# Charging.net
KiCad netlist of a schematic drawn in Altium Designer
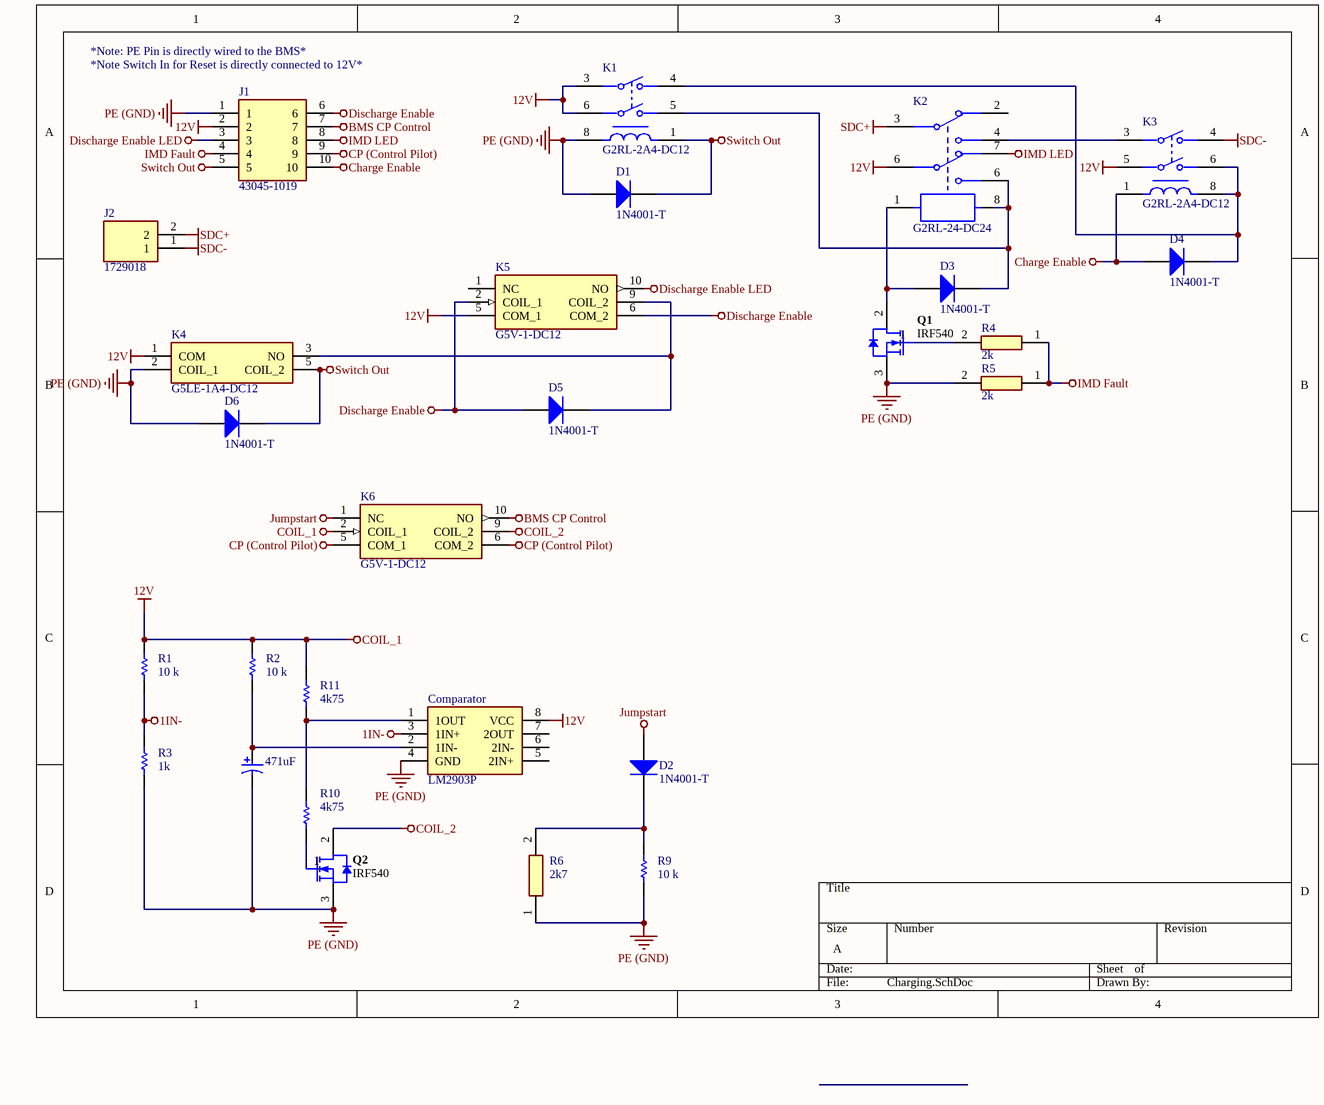
[diagram p0: Charging.SchDoc]

(export (version "E")
  (design (tool "Eeschema 10.0.6"))
  (components
    (comp (ref "471uF")
      (value "ECA-1JHG471")
      (footprint "CAPPR65-500-2000X1250X2200")
      (fields (field (name "MANUFACTURER") "Panasonic"))
      (libsource (lib "Altium Content Vault") (part "CAP-P-2"))
    )
    (comp (ref "Comparator")
      (value "LM2903P")
      (footprint "SamacSys:DIP794W53P254L959H508Q8N")
      (description "Integrated Circuit")
      (fields (field (name "MOUSER PART NUMBER") "595-LM2903P"))
      (libsource (lib "*") (part "LM2903P"))
    )
    (comp (ref "D1")
      (value "1N4001-T")
      (footprint "DIOD-DO-41-P-2_V")
      (description "1.0 A Rectifier, 15 pF, 50 V, -65 to 150 degC, 2-Pin DO-41 Plastic, RoHS, Tape and Reel")
      (fields (field (name "MANUFACTURER") "Diodes Inc"))
      (libsource (lib "Altium Content Vault") (part "DIOD-D-A1K2-2"))
    )
    (comp (ref "D2")
      (value "1N4001-T")
      (footprint "DIOD-DO-41-P-2_V")
      (description "1.0 A Rectifier, 15 pF, 50 V, -65 to 150 degC, 2-Pin DO-41 Plastic, RoHS, Tape and Reel")
      (fields (field (name "MANUFACTURER") "Diodes Inc"))
      (libsource (lib "Altium Content Vault") (part "DIOD-D-A1K2-2"))
    )
    (comp (ref "D3")
      (value "1N4001-T")
      (footprint "DIOD-DO-41-P-2_V")
      (description "1.0 A Rectifier, 15 pF, 50 V, -65 to 150 degC, 2-Pin DO-41 Plastic, RoHS, Tape and Reel")
      (fields (field (name "MANUFACTURER") "Diodes Inc"))
      (libsource (lib "Altium Content Vault") (part "DIOD-D-A1K2-2"))
    )
    (comp (ref "D4")
      (value "1N4001-T")
      (footprint "DIOD-DO-41-P-2_V")
      (description "1.0 A Rectifier, 15 pF, 50 V, -65 to 150 degC, 2-Pin DO-41 Plastic, RoHS, Tape and Reel")
      (fields (field (name "MANUFACTURER") "Diodes Inc"))
      (libsource (lib "Altium Content Vault") (part "DIOD-D-A1K2-2"))
    )
    (comp (ref "D5")
      (value "1N4001-T")
      (footprint "DIOD-DO-41-P-2_V")
      (description "1.0 A Rectifier, 15 pF, 50 V, -65 to 150 degC, 2-Pin DO-41 Plastic, RoHS, Tape and Reel")
      (fields (field (name "MANUFACTURER") "Diodes Inc"))
      (libsource (lib "Altium Content Vault") (part "DIOD-D-A1K2-2"))
    )
    (comp (ref "D6")
      (value "1N4001-T")
      (footprint "DIOD-DO-41-P-2_V")
      (description "1.0 A Rectifier, 15 pF, 50 V, -65 to 150 degC, 2-Pin DO-41 Plastic, RoHS, Tape and Reel")
      (fields (field (name "MANUFACTURER") "Diodes Inc"))
      (libsource (lib "Altium Content Vault") (part "DIOD-D-A1K2-2"))
    )
    (comp (ref "J1")
      (value "43045-1019")
      (footprint "SamacSys:43045-10YY_181920")
      (description "Connector")
      (fields (field (name "MOUSER PART NUMBER") "538-43045-1019"))
      (libsource (lib "*") (part "43045-1019"))
    )
    (comp (ref "J2")
      (value "1729018")
      (footprint "SamacSys:1729018")
      (description "Connector")
      (fields (field (name "MOUSER PART NUMBER") "651-1729018"))
      (libsource (lib "*") (part "1729018"))
    )
    (comp (ref "K1")
      (value "G2RL-2A4-DC12")
      (footprint "FP-G2RL-2A4-DC12-MFG")
      (description "RELAY GEN PURPOSE DPST 8A 12V")
      (libsource (lib "Altium Content Vault") (part "dfb52caf01785165d8ace8a37fe0b79"))
    )
    (comp (ref "K2")
      (value "G2RL-24-DC24")
      (footprint "OMRON-G2RL-24_V")
      (fields (field (name "MANUFACTURER") "Omron"))
      (libsource (lib "Altium Content Vault") (part "RELAY-DPDT-8_C"))
    )
    (comp (ref "K3")
      (value "G2RL-2A4-DC12")
      (footprint "FP-G2RL-2A4-DC12-MFG")
      (description "RELAY GEN PURPOSE DPST 8A 12V")
      (libsource (lib "") (part "dfb52caf01785165d8ace8a37fe0b79_1"))
    )
    (comp (ref "K4")
      (value "G5LE-1A4-DC12")
      (footprint "SamacSys:G5LE1A4DC12")
      (description "Relay or Contactor")
      (fields (field (name "MOUSER PART NUMBER") "653-G5LE-1A4-DC12"))
      (libsource (lib "*") (part "G5LE-1A4-DC12"))
    )
    (comp (ref "K5")
      (value "G5V-1-DC12")
      (footprint "SamacSys:G5V1DC12")
      (description "Relay or Contactor")
      (fields (field (name "MOUSER PART NUMBER") "653-G5V-1-DC12"))
      (libsource (lib "*") (part "G5V-1-DC12"))
    )
    (comp (ref "K6")
      (value "G5V-1-DC12")
      (footprint "SamacSys:G5V1DC12")
      (description "Relay or Contactor")
      (fields (field (name "MOUSER PART NUMBER") "653-G5V-1-DC12"))
      (libsource (lib "*") (part "G5V-1-DC12"))
    )
    (comp (ref "Q1")
      (value "IRF540")
      (footprint "VISH-TO-220AB-3_A")
      (description "Power MOSFET, 100 VDS, -55 to 175 degC, 3-Pin TO-220AB, RoHS, Tube")
      (fields (field (name "MANUFACTURER") "Vishay"))
      (libsource (lib "Altium Content Vault") (part "NEMOS-GDS-3"))
    )
    (comp (ref "Q2")
      (value "IRF540")
      (footprint "VISH-TO-220AB-3_A")
      (description "Power MOSFET, 100 VDS, -55 to 175 degC, 3-Pin TO-220AB, RoHS, Tube")
      (fields (field (name "MANUFACTURER") "Vishay"))
      (libsource (lib "Altium Content Vault") (part "NEMOS-GDS-3"))
    )
    (comp (ref "R1")
      (value "MFR-25FBF52-1K")
      (footprint "RESA60-630X240")
      (description "Axial Resistor, 1 KOhm, +/- 1%, 250 mW, -55 to 155 degC, 2-Pin THD, RoHS, Bulk")
      (fields (field (name "TOLERANCE") "1%") (field (name "RESISTANCE") "10 k"))
      (libsource (lib "Altium Content Vault") (part "RES-2"))
    )
    (comp (ref "R2")
      (value "MFR-25FBF52-1K")
      (footprint "RESA60-630X240")
      (description "Axial Resistor, 1 KOhm, +/- 1%, 250 mW, -55 to 155 degC, 2-Pin THD, RoHS, Bulk")
      (fields (field (name "TOLERANCE") "1%") (field (name "RESISTANCE") "10 k"))
      (libsource (lib "Altium Content Vault") (part "RES-2"))
    )
    (comp (ref "R3")
      (value "MFR-25FBF52-1K")
      (footprint "RESA60-630X240")
      (description "Axial Resistor, 1 KOhm, +/- 1%, 250 mW, -55 to 155 degC, 2-Pin THD, RoHS, Bulk")
      (fields (field (name "TOLERANCE") "1%") (field (name "RESISTANCE") "1k"))
      (libsource (lib "Altium Content Vault") (part "RES-2"))
    )
    (comp (ref "R4")
      (value "MFR-25FBF52-2K")
      (footprint "SamacSys:RESAD1590W60L630D240")
      (description "Resistor")
      (fields (field (name "RESISTANCE") "2k"))
      (libsource (lib "*") (part "MFR-25FBF52-2K"))
    )
    (comp (ref "R5")
      (value "MFR-25FBF52-2K")
      (footprint "SamacSys:RESAD1590W60L630D240")
      (description "Resistor")
      (fields (field (name "RESISTANCE") "2k"))
      (libsource (lib "*") (part "MFR-25FBF52-2K"))
    )
    (comp (ref "R6")
      (value "2.7k")
      (footprint "SamacSys:RESAD1590W60L630D240")
      (description "Resistor")
      (fields
        (field (name "MANUFACTURER_PART_NUMBER") "CFR-25JB-52-2K7")
        (field (name "MOUSER PART NUMBER") "603-CFR-25JB-52-2K7")
        (field (name "RESISTANCE") "2k7")
      )
      (libsource (lib "*") (part "CFR-25JB-52-2K7"))
    )
    (comp (ref "R9")
      (value "MFR-25FBF52-1K")
      (footprint "RESA60-630X240")
      (description "Axial Resistor, 1 KOhm, +/- 1%, 250 mW, -55 to 155 degC, 2-Pin THD, RoHS, Bulk")
      (fields (field (name "TOLERANCE") "1%") (field (name "RESISTANCE") "10 k"))
      (libsource (lib "Altium Content Vault") (part "RES-2"))
    )
    (comp (ref "R10")
      (value "4.75 k")
      (footprint "RESA60-630X240")
      (description "Axial Resistor, 4.75 KOhm, +/- 1%, 0.25 W, -55 to 155 degC, 2-Pin THD, RoHS, Bulk")
      (fields (field (name "TOLERANCE") "10%") (field (name "RESISTANCE") "4k75"))
      (libsource (lib "Altium Content Vault") (part "RES-2"))
    )
    (comp (ref "R11")
      (value "4.75 k")
      (footprint "RESA60-630X240")
      (description "Axial Resistor, 4.75 KOhm, +/- 1%, 0.25 W, -55 to 155 degC, 2-Pin THD, RoHS, Bulk")
      (fields (field (name "TOLERANCE") "10%") (field (name "RESISTANCE") "4k75"))
      (libsource (lib "Altium Content Vault") (part "RES-2"))
    )
  )
  (nets
    (net (code "1") (name "1IN-") (class "Default")
      (node (ref "Comparator") (pin "3") (pinfunction "1IN+_3") (pintype "passive"))
      (node (ref "R1") (pin "1") (pinfunction "1_1") (pintype "passive"))
      (node (ref "R3") (pin "2") (pinfunction "2_2") (pintype "passive"))
    )
    (net (code "2") (name "12V") (class "Default")
      (node (ref "Comparator") (pin "8") (pinfunction "VCC_8") (pintype "passive"))
      (node (ref "J1") (pin "2") (pinfunction "2_2") (pintype "passive"))
      (node (ref "K1") (pin "3") (pinfunction "3_3") (pintype "passive"))
      (node (ref "K1") (pin "6") (pinfunction "6_6") (pintype "passive"))
      (node (ref "K2") (pin "6") (pinfunction "6_6") (pintype "passive"))
      (node (ref "K3") (pin "5") (pinfunction "5_5") (pintype "passive"))
      (node (ref "K4") (pin "1") (pinfunction "COM_1") (pintype "passive"))
      (node (ref "K5") (pin "5") (pinfunction "COM_1_5") (pintype "passive"))
      (node (ref "K6") (pin "2") (pinfunction "COIL_1_2") (pintype "input"))
      (node (ref "R1") (pin "2") (pinfunction "2_2") (pintype "passive"))
      (node (ref "R11") (pin "2") (pinfunction "2_2") (pintype "passive"))
      (node (ref "R2") (pin "2") (pinfunction "2_2") (pintype "passive"))
    )
    (net (code "3") (name "BMS CP Control") (class "Default")
      (node (ref "J1") (pin "7") (pinfunction "7_7") (pintype "passive"))
      (node (ref "K6") (pin "10") (pinfunction "NO_10") (pintype "output"))
    )
    (net (code "4") (name "COIL_2") (class "Default")
      (node (ref "K6") (pin "9") (pinfunction "COIL_2_9") (pintype "power_in"))
      (node (ref "Q2") (pin "2") (pinfunction "D_2") (pintype "passive"))
    )
    (net (code "5") (name "CP (Control Pilot)") (class "Default")
      (node (ref "J1") (pin "9") (pinfunction "9_9") (pintype "passive"))
      (node (ref "K6") (pin "5") (pinfunction "COM_1_5") (pintype "passive"))
      (node (ref "K6") (pin "6") (pinfunction "COM_2_6") (pintype "passive"))
    )
    (net (code "6") (name "Charge Enable") (class "Default")
      (node (ref "D4") (pin "1") (pinfunction "A_1") (pintype "passive"))
      (node (ref "J1") (pin "10") (pinfunction "10_10") (pintype "passive"))
      (node (ref "K3") (pin "1") (pinfunction "1_1") (pintype "passive"))
    )
    (net (code "7") (name "Discharge Enable") (class "Default")
      (node (ref "D5") (pin "1") (pinfunction "A_1") (pintype "passive"))
      (node (ref "J1") (pin "6") (pinfunction "6_6") (pintype "passive"))
      (node (ref "K5") (pin "2") (pinfunction "COIL_1_2") (pintype "input"))
      (node (ref "K5") (pin "6") (pinfunction "COM_2_6") (pintype "passive"))
    )
    (net (code "8") (name "Discharge Enable LED") (class "Default")
      (node (ref "J1") (pin "3") (pinfunction "3_3") (pintype "passive"))
      (node (ref "K5") (pin "10") (pinfunction "NO_10") (pintype "output"))
    )
    (net (code "9") (name "IMD Fault") (class "Default")
      (node (ref "J1") (pin "4") (pinfunction "4_4") (pintype "passive"))
      (node (ref "R4") (pin "1") (pinfunction "1_1") (pintype "passive"))
      (node (ref "R5") (pin "1") (pinfunction "1_1") (pintype "passive"))
    )
    (net (code "10") (name "IMD LED") (class "Default")
      (node (ref "J1") (pin "8") (pinfunction "8_8") (pintype "passive"))
      (node (ref "K2") (pin "7") (pinfunction "7_7") (pintype "passive"))
    )
    (net (code "11") (name "Jumpstart") (class "Default")
      (node (ref "D2") (pin "1") (pinfunction "A_1") (pintype "passive"))
      (node (ref "K6") (pin "1") (pinfunction "NC_1") (pintype "passive"))
    )
    (net (code "12") (name "Net-(Comparator-1IN-)") (class "Default")
      (node (ref "471uF") (pin "1") (pinfunction "1_1") (pintype "passive"))
      (node (ref "Comparator") (pin "2") (pinfunction "1IN-_2") (pintype "passive"))
      (node (ref "R2") (pin "1") (pinfunction "1_1") (pintype "passive"))
    )
    (net (code "13") (name "Net-(Comparator-1OUT)") (class "Default")
      (node (ref "Comparator") (pin "1") (pinfunction "1OUT_1") (pintype "passive"))
      (node (ref "R10") (pin "1") (pinfunction "1_1") (pintype "passive"))
      (node (ref "R11") (pin "1") (pinfunction "1_1") (pintype "passive"))
    )
    (net (code "14") (name "Net-(D2-K)") (class "Default")
      (node (ref "D2") (pin "2") (pinfunction "K_2") (pintype "passive"))
      (node (ref "R6") (pin "2") (pinfunction "2_2") (pintype "passive"))
      (node (ref "R9") (pin "2") (pinfunction "2_2") (pintype "passive"))
    )
    (net (code "15") (name "Net-(D3-A)") (class "Default")
      (node (ref "D3") (pin "1") (pinfunction "A_1") (pintype "passive"))
      (node (ref "K2") (pin "1") (pinfunction "1_1") (pintype "passive"))
      (node (ref "Q1") (pin "2") (pinfunction "D_2") (pintype "passive"))
    )
    (net (code "16") (name "Net-(D3-K)") (class "Default")
      (node (ref "D3") (pin "2") (pinfunction "K_2") (pintype "passive"))
      (node (ref "K1") (pin "5") (pinfunction "5_5") (pintype "passive"))
      (node (ref "K2") (pin "6") (pinfunction "6_6") (pintype "passive"))
      (node (ref "K2") (pin "8") (pinfunction "8_8") (pintype "passive"))
    )
    (net (code "17") (name "Net-(D4-K)") (class "Default")
      (node (ref "D4") (pin "2") (pinfunction "K_2") (pintype "passive"))
      (node (ref "K1") (pin "4") (pinfunction "4_4") (pintype "passive"))
      (node (ref "K3") (pin "6") (pinfunction "6_6") (pintype "passive"))
      (node (ref "K3") (pin "8") (pinfunction "8_8") (pintype "passive"))
    )
    (net (code "18") (name "Net-(D5-K)") (class "Default")
      (node (ref "D5") (pin "2") (pinfunction "K_2") (pintype "passive"))
      (node (ref "K4") (pin "3") (pinfunction "NO_3") (pintype "passive"))
      (node (ref "K5") (pin "9") (pinfunction "COIL_2_9") (pintype "power_in"))
    )
    (net (code "19") (name "Net-(K2-Pad4)") (class "Default")
      (node (ref "K2") (pin "4") (pinfunction "4_4") (pintype "passive"))
      (node (ref "K3") (pin "3") (pinfunction "3_3") (pintype "passive"))
    )
    (net (code "20") (name "Net-(Q1-G)") (class "Default")
      (node (ref "Q1") (pin "1") (pinfunction "G_1") (pintype "passive"))
      (node (ref "R4") (pin "2") (pinfunction "2_2") (pintype "passive"))
    )
    (net (code "21") (name "Net-(Q2-G)") (class "Default")
      (node (ref "Q2") (pin "1") (pinfunction "G_1") (pintype "passive"))
      (node (ref "R10") (pin "2") (pinfunction "2_2") (pintype "passive"))
    )
    (net (code "22") (name "PE (GND)") (class "Default")
      (node (ref "471uF") (pin "2") (pinfunction "2_2") (pintype "passive"))
      (node (ref "Comparator") (pin "4") (pinfunction "GND_4") (pintype "passive"))
      (node (ref "D1") (pin "1") (pinfunction "A_1") (pintype "passive"))
      (node (ref "D6") (pin "1") (pinfunction "A_1") (pintype "passive"))
      (node (ref "J1") (pin "1") (pinfunction "1_1") (pintype "passive"))
      (node (ref "K1") (pin "8") (pinfunction "8_8") (pintype "passive"))
      (node (ref "K4") (pin "2") (pinfunction "COIL_1_2") (pintype "passive"))
      (node (ref "Q1") (pin "3") (pinfunction "S_3") (pintype "passive"))
      (node (ref "Q2") (pin "3") (pinfunction "S_3") (pintype "passive"))
      (node (ref "R3") (pin "1") (pinfunction "1_1") (pintype "passive"))
      (node (ref "R5") (pin "2") (pinfunction "2_2") (pintype "passive"))
      (node (ref "R6") (pin "1") (pinfunction "1_1") (pintype "passive"))
      (node (ref "R9") (pin "1") (pinfunction "1_1") (pintype "passive"))
    )
    (net (code "23") (name "SDC+") (class "Default")
      (node (ref "J2") (pin "2") (pinfunction "2_2") (pintype "passive"))
      (node (ref "K2") (pin "3") (pinfunction "3_3") (pintype "passive"))
    )
    (net (code "24") (name "SDC-") (class "Default")
      (node (ref "J2") (pin "1") (pinfunction "1_1") (pintype "passive"))
      (node (ref "K3") (pin "4") (pinfunction "4_4") (pintype "passive"))
    )
    (net (code "25") (name "Switch Out") (class "Default")
      (node (ref "D1") (pin "2") (pinfunction "K_2") (pintype "passive"))
      (node (ref "D6") (pin "2") (pinfunction "K_2") (pintype "passive"))
      (node (ref "J1") (pin "5") (pinfunction "5_5") (pintype "passive"))
      (node (ref "K1") (pin "1") (pinfunction "1_1") (pintype "passive"))
      (node (ref "K4") (pin "5") (pinfunction "COIL_2_5") (pintype "passive"))
    )
    (net (code "26") (name "unconnected-(Comparator-2IN+-Pad5)") (class "Default")
      (node (ref "Comparator") (pin "5") (pinfunction "2IN+_5") (pintype "passive"))
    )
    (net (code "27") (name "unconnected-(Comparator-2IN--Pad6)") (class "Default")
      (node (ref "Comparator") (pin "6") (pinfunction "2IN-_6") (pintype "passive"))
    )
    (net (code "28") (name "unconnected-(Comparator-2OUT-Pad7)") (class "Default")
      (node (ref "Comparator") (pin "7") (pinfunction "2OUT_7") (pintype "passive"))
    )
    (net (code "29") (name "unconnected-(K2-Pad2)") (class "Default")
      (node (ref "K2") (pin "2") (pinfunction "2_2") (pintype "passive"))
    )
    (net (code "30") (name "unconnected-(K5-NC-Pad1)") (class "Default")
      (node (ref "K5") (pin "1") (pinfunction "NC_1") (pintype "passive"))
    )
  )
)
